# Adafruit_TXB0108.net
KiCad netlist of a schematic drawn in EAGLE
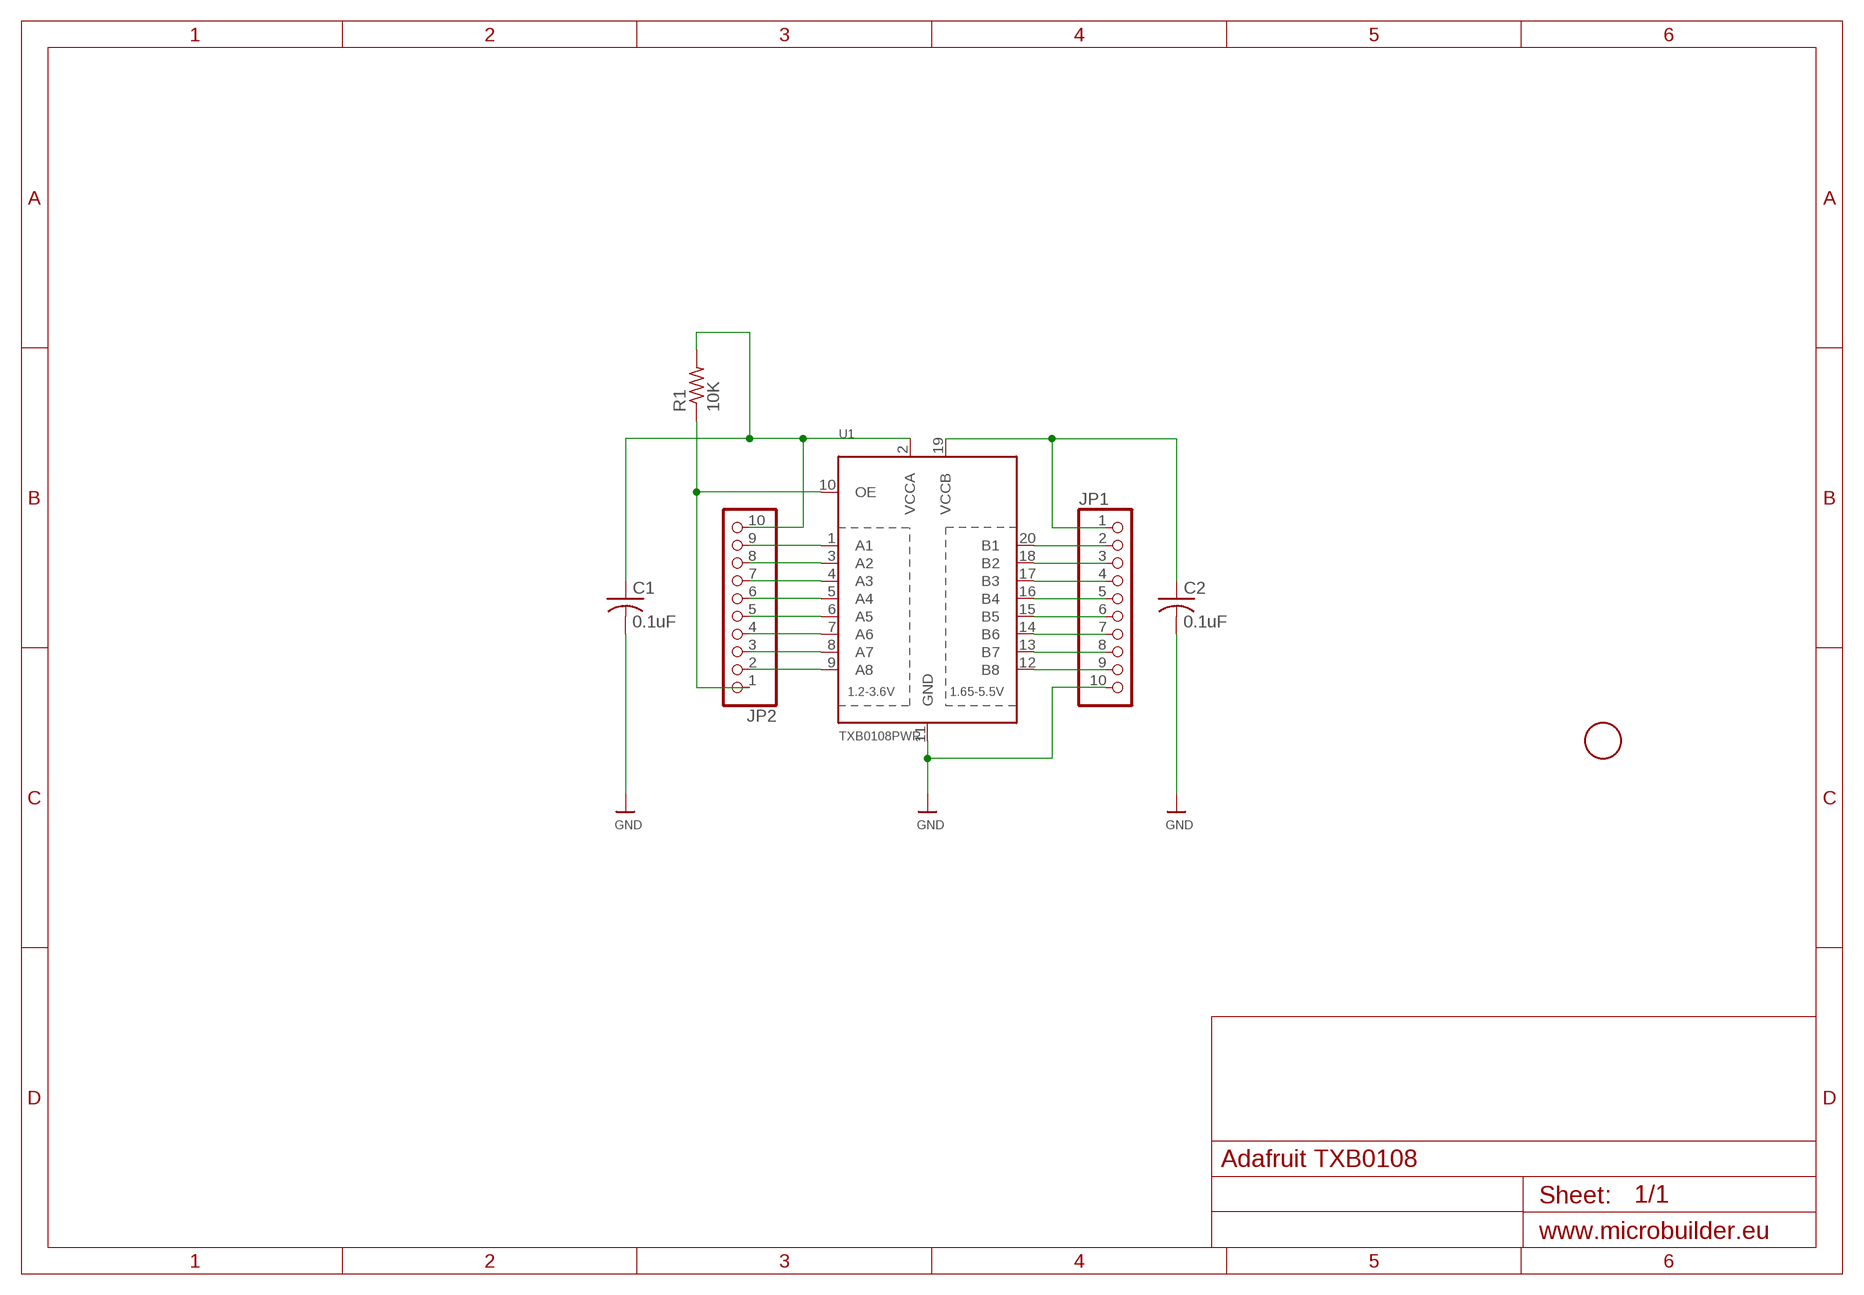
[diagram p0: schematic, sheet 1]

(export (version "E")
  (design (tool "Eeschema 10.0.6"))
  (components
    (comp (ref "C1")
      (value "0.1uF")
      (footprint "eagle-import:C0805")
      (libsource (lib "eagle-import") (part "C-USC0805"))
    )
    (comp (ref "C2")
      (value "0.1uF")
      (footprint "eagle-import:C0805")
      (libsource (lib "eagle-import") (part "C-USC0805"))
    )
    (comp (ref "JP1")
      (value "HEADER-1X10THICKER")
      (footprint "eagle-import:1X10_ROUND_76")
      (libsource (lib "eagle-import") (part "HEADER-1X10THICKER"))
    )
    (comp (ref "JP2")
      (value "HEADER-1X10THICKER")
      (footprint "eagle-import:1X10_ROUND_76")
      (libsource (lib "eagle-import") (part "HEADER-1X10THICKER"))
    )
    (comp (ref "R1")
      (value "10K")
      (footprint "eagle-import:R0805")
      (libsource (lib "eagle-import") (part "R-US_R0805"))
    )
    (comp (ref "U$6")
      (value "FIDUCIAL")
      (footprint "eagle-import:FIDUCIAL_1MM")
      (libsource (lib "eagle-import") (part "FIDUCIAL"))
    )
    (comp (ref "U1")
      (value "TXB0108PWR")
      (footprint "eagle-import:TSSOP20")
      (libsource (lib "eagle-import") (part "TXB0108PWR"))
    )
  )
  (nets
    (net (code "1") (name "GND") (class "Default")
      (node (ref "C1") (pin "2") (pinfunction "2_2") (pintype "passive"))
      (node (ref "C2") (pin "2") (pinfunction "2_2") (pintype "passive"))
      (node (ref "JP1") (pin "10") (pinfunction "10_10") (pintype "passive"))
      (node (ref "U1") (pin "11") (pinfunction "GND_11") (pintype "bidirectional"))
    )
    (net (code "2") (name "Net-(U1-A1)") (class "Default")
      (node (ref "JP2") (pin "9") (pinfunction "9_9") (pintype "passive"))
      (node (ref "U1") (pin "1") (pinfunction "A1_1") (pintype "bidirectional"))
    )
    (net (code "3") (name "Net-(U1-A2)") (class "Default")
      (node (ref "JP2") (pin "8") (pinfunction "8_8") (pintype "passive"))
      (node (ref "U1") (pin "3") (pinfunction "A2_3") (pintype "bidirectional"))
    )
    (net (code "4") (name "Net-(U1-A3)") (class "Default")
      (node (ref "JP2") (pin "7") (pinfunction "7_7") (pintype "passive"))
      (node (ref "U1") (pin "4") (pinfunction "A3_4") (pintype "bidirectional"))
    )
    (net (code "5") (name "Net-(U1-A4)") (class "Default")
      (node (ref "JP2") (pin "6") (pinfunction "6_6") (pintype "passive"))
      (node (ref "U1") (pin "5") (pinfunction "A4_5") (pintype "bidirectional"))
    )
    (net (code "6") (name "Net-(U1-A5)") (class "Default")
      (node (ref "JP2") (pin "5") (pinfunction "5_5") (pintype "passive"))
      (node (ref "U1") (pin "6") (pinfunction "A5_6") (pintype "bidirectional"))
    )
    (net (code "7") (name "Net-(U1-A6)") (class "Default")
      (node (ref "JP2") (pin "4") (pinfunction "4_4") (pintype "passive"))
      (node (ref "U1") (pin "7") (pinfunction "A6_7") (pintype "bidirectional"))
    )
    (net (code "8") (name "Net-(U1-A7)") (class "Default")
      (node (ref "JP2") (pin "3") (pinfunction "3_3") (pintype "passive"))
      (node (ref "U1") (pin "8") (pinfunction "A7_8") (pintype "bidirectional"))
    )
    (net (code "9") (name "Net-(U1-A8)") (class "Default")
      (node (ref "JP2") (pin "2") (pinfunction "2_2") (pintype "passive"))
      (node (ref "U1") (pin "9") (pinfunction "A8_9") (pintype "bidirectional"))
    )
    (net (code "10") (name "Net-(U1-B1)") (class "Default")
      (node (ref "JP1") (pin "2") (pinfunction "2_2") (pintype "passive"))
      (node (ref "U1") (pin "20") (pinfunction "B1_20") (pintype "bidirectional"))
    )
    (net (code "11") (name "Net-(U1-B2)") (class "Default")
      (node (ref "JP1") (pin "3") (pinfunction "3_3") (pintype "passive"))
      (node (ref "U1") (pin "18") (pinfunction "B2_18") (pintype "bidirectional"))
    )
    (net (code "12") (name "Net-(U1-B3)") (class "Default")
      (node (ref "JP1") (pin "4") (pinfunction "4_4") (pintype "passive"))
      (node (ref "U1") (pin "17") (pinfunction "B3_17") (pintype "bidirectional"))
    )
    (net (code "13") (name "Net-(U1-B4)") (class "Default")
      (node (ref "JP1") (pin "5") (pinfunction "5_5") (pintype "passive"))
      (node (ref "U1") (pin "16") (pinfunction "B4_16") (pintype "bidirectional"))
    )
    (net (code "14") (name "Net-(U1-B5)") (class "Default")
      (node (ref "JP1") (pin "6") (pinfunction "6_6") (pintype "passive"))
      (node (ref "U1") (pin "15") (pinfunction "B5_15") (pintype "bidirectional"))
    )
    (net (code "15") (name "Net-(U1-B6)") (class "Default")
      (node (ref "JP1") (pin "7") (pinfunction "7_7") (pintype "passive"))
      (node (ref "U1") (pin "14") (pinfunction "B6_14") (pintype "bidirectional"))
    )
    (net (code "16") (name "Net-(U1-B7)") (class "Default")
      (node (ref "JP1") (pin "8") (pinfunction "8_8") (pintype "passive"))
      (node (ref "U1") (pin "13") (pinfunction "B7_13") (pintype "bidirectional"))
    )
    (net (code "17") (name "Net-(U1-B8)") (class "Default")
      (node (ref "JP1") (pin "9") (pinfunction "9_9") (pintype "passive"))
      (node (ref "U1") (pin "12") (pinfunction "B8_12") (pintype "bidirectional"))
    )
    (net (code "18") (name "Net-(U1-OE)") (class "Default")
      (node (ref "JP2") (pin "1") (pinfunction "1_1") (pintype "passive"))
      (node (ref "R1") (pin "1") (pinfunction "1_1") (pintype "passive"))
      (node (ref "U1") (pin "10") (pinfunction "OE_10") (pintype "bidirectional"))
    )
    (net (code "19") (name "Net-(U1-VCCA)") (class "Default")
      (node (ref "C1") (pin "1") (pinfunction "1_1") (pintype "passive"))
      (node (ref "JP2") (pin "10") (pinfunction "10_10") (pintype "passive"))
      (node (ref "R1") (pin "2") (pinfunction "2_2") (pintype "passive"))
      (node (ref "U1") (pin "2") (pinfunction "VCCA_2") (pintype "bidirectional"))
    )
    (net (code "20") (name "Net-(U1-VCCB)") (class "Default")
      (node (ref "C2") (pin "1") (pinfunction "1_1") (pintype "passive"))
      (node (ref "JP1") (pin "1") (pinfunction "1_1") (pintype "passive"))
      (node (ref "U1") (pin "19") (pinfunction "VCCB_19") (pintype "bidirectional"))
    )
  )
)
